# RaspberryPi-PICPgm.net
KiCad netlist of a schematic drawn in EAGLE
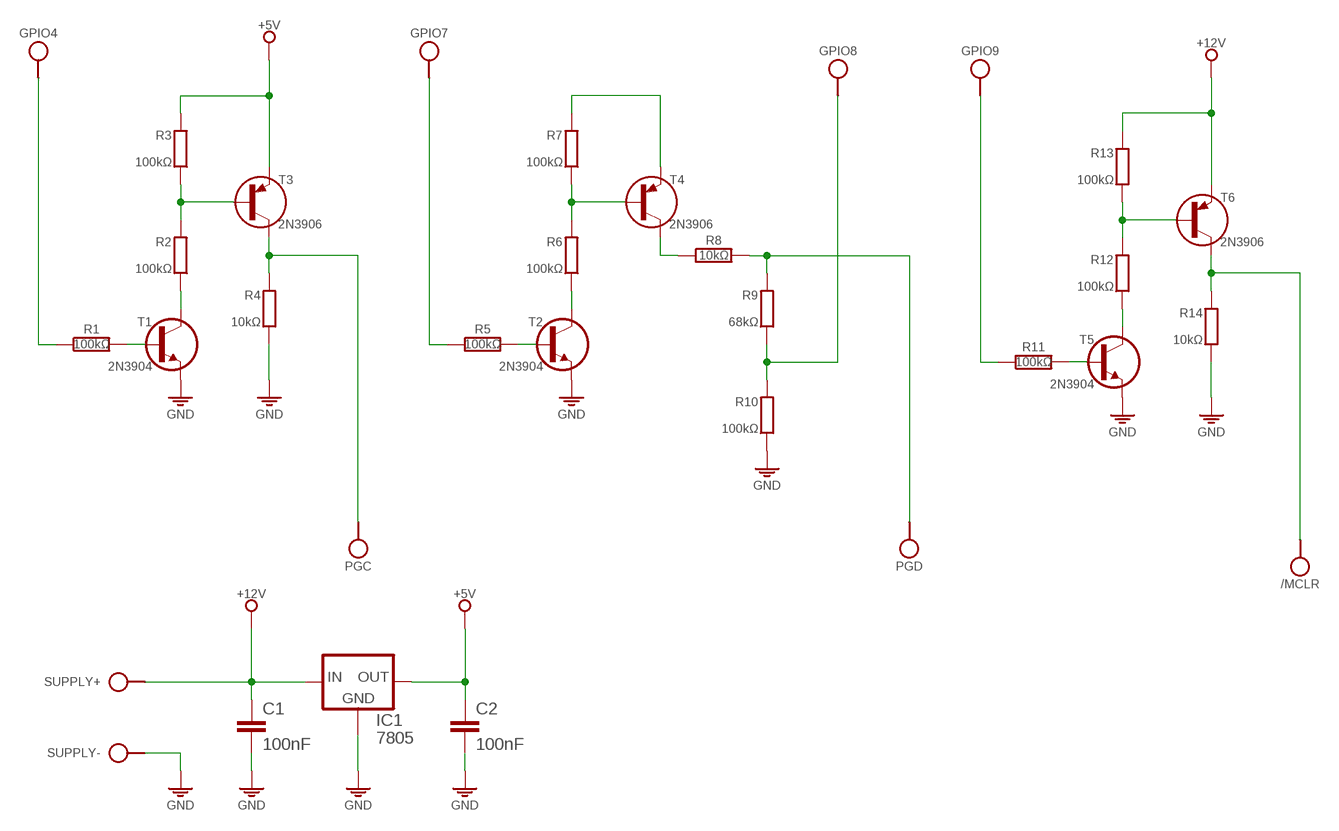
[diagram p0: schematic, sheet 1]

(export (version "E")
  (design (tool "Eeschema 10.0.6"))
  (components
    (comp (ref "/MCLR")
      (value "VPORT")
      (footprint "eagle-import:SPAD")
      (libsource (lib "eagle-import") (part "VPORT"))
    )
    (comp (ref "C1")
      (value "100nF")
      (footprint "eagle-import:C050-025X075")
      (libsource (lib "eagle-import") (part "C050-025X075"))
    )
    (comp (ref "C2")
      (value "100nF")
      (footprint "eagle-import:C050-025X075")
      (libsource (lib "eagle-import") (part "C050-025X075"))
    )
    (comp (ref "GPIO4")
      (value "VPORT")
      (footprint "eagle-import:SPAD")
      (libsource (lib "eagle-import") (part "VPORT"))
    )
    (comp (ref "GPIO7")
      (value "VPORT")
      (footprint "eagle-import:SPAD")
      (libsource (lib "eagle-import") (part "VPORT"))
    )
    (comp (ref "GPIO8")
      (value "VPORT")
      (footprint "eagle-import:SPAD")
      (libsource (lib "eagle-import") (part "VPORT"))
    )
    (comp (ref "GPIO9")
      (value "VPORT")
      (footprint "eagle-import:SPAD")
      (libsource (lib "eagle-import") (part "VPORT"))
    )
    (comp (ref "IC1")
      (value "7805")
      (footprint "eagle-import:TO220")
      (libsource (lib "eagle-import") (part "LM78"))
    )
    (comp (ref "PGC")
      (value "VPORT")
      (footprint "eagle-import:SPAD")
      (libsource (lib "eagle-import") (part "VPORT"))
    )
    (comp (ref "PGD")
      (value "VPORT")
      (footprint "eagle-import:SPAD")
      (libsource (lib "eagle-import") (part "VPORT"))
    )
    (comp (ref "R1")
      (value "100kΩ")
      (footprint "eagle-import:0204_10")
      (libsource (lib "eagle-import") (part "R-H0204/10"))
    )
    (comp (ref "R2")
      (value "100kΩ")
      (footprint "eagle-import:0204_10-V")
      (libsource (lib "eagle-import") (part "R0204/10-V"))
    )
    (comp (ref "R3")
      (value "100kΩ")
      (footprint "eagle-import:0204_10-V")
      (libsource (lib "eagle-import") (part "R0204/10-V"))
    )
    (comp (ref "R4")
      (value "10kΩ")
      (footprint "eagle-import:0204_10-V")
      (libsource (lib "eagle-import") (part "R0204/10-V"))
    )
    (comp (ref "R5")
      (value "100kΩ")
      (footprint "eagle-import:0204_10")
      (libsource (lib "eagle-import") (part "R-H0204/10"))
    )
    (comp (ref "R6")
      (value "100kΩ")
      (footprint "eagle-import:0204_10-V")
      (libsource (lib "eagle-import") (part "R0204/10-V"))
    )
    (comp (ref "R7")
      (value "100kΩ")
      (footprint "eagle-import:0204_10-V")
      (libsource (lib "eagle-import") (part "R0204/10-V"))
    )
    (comp (ref "R8")
      (value "10kΩ")
      (footprint "eagle-import:0204_10")
      (libsource (lib "eagle-import") (part "R-H0204/10"))
    )
    (comp (ref "R9")
      (value "68kΩ")
      (footprint "eagle-import:0204_10-V")
      (libsource (lib "eagle-import") (part "R0204/10-V"))
    )
    (comp (ref "R10")
      (value "100kΩ")
      (footprint "eagle-import:0204_10-V")
      (libsource (lib "eagle-import") (part "R0204/10-V"))
    )
    (comp (ref "R11")
      (value "100kΩ")
      (footprint "eagle-import:0204_10")
      (libsource (lib "eagle-import") (part "R-H0204/10"))
    )
    (comp (ref "R12")
      (value "100kΩ")
      (footprint "eagle-import:0204_10-V")
      (libsource (lib "eagle-import") (part "R0204/10-V"))
    )
    (comp (ref "R13")
      (value "100kΩ")
      (footprint "eagle-import:0204_10-V")
      (libsource (lib "eagle-import") (part "R0204/10-V"))
    )
    (comp (ref "R14")
      (value "10kΩ")
      (footprint "eagle-import:0204_10-V")
      (libsource (lib "eagle-import") (part "R0204/10-V"))
    )
    (comp (ref "SUPPLY")
      (value "SPAD+--+")
      (footprint "eagle-import:SPAD-+")
      (libsource (lib "eagle-import") (part "SPAD+--+"))
    )
    (comp (ref "T1")
      (value "2N3904")
      (footprint "eagle-import:TO92")
      (libsource (lib "eagle-import") (part "2N3904"))
    )
    (comp (ref "T2")
      (value "2N3904")
      (footprint "eagle-import:TO92")
      (libsource (lib "eagle-import") (part "2N3904"))
    )
    (comp (ref "T3")
      (value "2N3906")
      (footprint "eagle-import:TO92")
      (libsource (lib "eagle-import") (part "2N3906"))
    )
    (comp (ref "T4")
      (value "2N3906")
      (footprint "eagle-import:TO92")
      (libsource (lib "eagle-import") (part "2N3906"))
    )
    (comp (ref "T5")
      (value "2N3904")
      (footprint "eagle-import:TO92")
      (libsource (lib "eagle-import") (part "2N3904"))
    )
    (comp (ref "T6")
      (value "2N3906")
      (footprint "eagle-import:TO92")
      (libsource (lib "eagle-import") (part "2N3906"))
    )
  )
  (nets
    (net (code "1") (name "+5V") (class "Default")
      (node (ref "C2") (pin "1") (pinfunction "1_1") (pintype "passive"))
      (node (ref "IC1") (pin "3") (pinfunction "OUT_3") (pintype "output"))
      (node (ref "R3") (pin "1") (pinfunction "2_1") (pintype "passive"))
      (node (ref "R7") (pin "1") (pinfunction "2_1") (pintype "passive"))
      (node (ref "T3") (pin "1") (pinfunction "E_1") (pintype "passive"))
      (node (ref "T4") (pin "1") (pinfunction "E_1") (pintype "passive"))
    )
    (net (code "2") (name "+12V") (class "Default")
      (node (ref "C1") (pin "1") (pinfunction "1_1") (pintype "passive"))
      (node (ref "IC1") (pin "1") (pinfunction "IN_1") (pintype "input"))
      (node (ref "R13") (pin "1") (pinfunction "2_1") (pintype "passive"))
      (node (ref "SUPPLY") (pin "2") (pinfunction "P$1_2") (pintype "passive"))
      (node (ref "T6") (pin "1") (pinfunction "E_1") (pintype "passive"))
    )
    (net (code "3") (name "GND") (class "Default")
      (node (ref "C1") (pin "2") (pinfunction "2_2") (pintype "passive"))
      (node (ref "C2") (pin "2") (pinfunction "2_2") (pintype "passive"))
      (node (ref "IC1") (pin "2") (pinfunction "GND_2") (pintype "input"))
      (node (ref "R10") (pin "2") (pinfunction "1_2") (pintype "passive"))
      (node (ref "R14") (pin "2") (pinfunction "1_2") (pintype "passive"))
      (node (ref "R4") (pin "2") (pinfunction "1_2") (pintype "passive"))
      (node (ref "SUPPLY") (pin "1") (pinfunction "P$1_1") (pintype "passive"))
      (node (ref "T1") (pin "1") (pinfunction "E_1") (pintype "passive"))
      (node (ref "T2") (pin "1") (pinfunction "E_1") (pintype "passive"))
      (node (ref "T5") (pin "1") (pinfunction "E_1") (pintype "passive"))
    )
    (net (code "4") (name "Net-(/MCLR-P$1)") (class "Default")
      (node (ref "/MCLR") (pin "1") (pinfunction "P$1_1") (pintype "passive"))
      (node (ref "R14") (pin "1") (pinfunction "2_1") (pintype "passive"))
      (node (ref "T6") (pin "3") (pinfunction "C_3") (pintype "passive"))
    )
    (net (code "5") (name "Net-(GPIO4-P$1)") (class "Default")
      (node (ref "GPIO4") (pin "1") (pinfunction "P$1_1") (pintype "passive"))
      (node (ref "R1") (pin "1") (pinfunction "1_1") (pintype "passive"))
    )
    (net (code "6") (name "Net-(GPIO7-P$1)") (class "Default")
      (node (ref "GPIO7") (pin "1") (pinfunction "P$1_1") (pintype "passive"))
      (node (ref "R5") (pin "1") (pinfunction "1_1") (pintype "passive"))
    )
    (net (code "7") (name "Net-(GPIO8-P$1)") (class "Default")
      (node (ref "GPIO8") (pin "1") (pinfunction "P$1_1") (pintype "passive"))
      (node (ref "R10") (pin "1") (pinfunction "2_1") (pintype "passive"))
      (node (ref "R9") (pin "2") (pinfunction "1_2") (pintype "passive"))
    )
    (net (code "8") (name "Net-(GPIO9-P$1)") (class "Default")
      (node (ref "GPIO9") (pin "1") (pinfunction "P$1_1") (pintype "passive"))
      (node (ref "R11") (pin "1") (pinfunction "1_1") (pintype "passive"))
    )
    (net (code "9") (name "Net-(PGC-P$1)") (class "Default")
      (node (ref "PGC") (pin "1") (pinfunction "P$1_1") (pintype "passive"))
      (node (ref "R4") (pin "1") (pinfunction "2_1") (pintype "passive"))
      (node (ref "T3") (pin "3") (pinfunction "C_3") (pintype "passive"))
    )
    (net (code "10") (name "Net-(PGD-P$1)") (class "Default")
      (node (ref "PGD") (pin "1") (pinfunction "P$1_1") (pintype "passive"))
      (node (ref "R8") (pin "2") (pinfunction "2_2") (pintype "passive"))
      (node (ref "R9") (pin "1") (pinfunction "2_1") (pintype "passive"))
    )
    (net (code "11") (name "Net-(R2-1)") (class "Default")
      (node (ref "R2") (pin "2") (pinfunction "1_2") (pintype "passive"))
      (node (ref "T1") (pin "3") (pinfunction "C_3") (pintype "passive"))
    )
    (net (code "12") (name "Net-(R2-2)") (class "Default")
      (node (ref "R2") (pin "1") (pinfunction "2_1") (pintype "passive"))
      (node (ref "R3") (pin "2") (pinfunction "1_2") (pintype "passive"))
      (node (ref "T3") (pin "2") (pinfunction "B_2") (pintype "passive"))
    )
    (net (code "13") (name "Net-(R6-1)") (class "Default")
      (node (ref "R6") (pin "2") (pinfunction "1_2") (pintype "passive"))
      (node (ref "T2") (pin "3") (pinfunction "C_3") (pintype "passive"))
    )
    (net (code "14") (name "Net-(R6-2)") (class "Default")
      (node (ref "R6") (pin "1") (pinfunction "2_1") (pintype "passive"))
      (node (ref "R7") (pin "2") (pinfunction "1_2") (pintype "passive"))
      (node (ref "T4") (pin "2") (pinfunction "B_2") (pintype "passive"))
    )
    (net (code "15") (name "Net-(R12-1)") (class "Default")
      (node (ref "R12") (pin "2") (pinfunction "1_2") (pintype "passive"))
      (node (ref "T5") (pin "3") (pinfunction "C_3") (pintype "passive"))
    )
    (net (code "16") (name "Net-(R12-2)") (class "Default")
      (node (ref "R12") (pin "1") (pinfunction "2_1") (pintype "passive"))
      (node (ref "R13") (pin "2") (pinfunction "1_2") (pintype "passive"))
      (node (ref "T6") (pin "2") (pinfunction "B_2") (pintype "passive"))
    )
    (net (code "17") (name "Net-(T1-B)") (class "Default")
      (node (ref "R1") (pin "2") (pinfunction "2_2") (pintype "passive"))
      (node (ref "T1") (pin "2") (pinfunction "B_2") (pintype "passive"))
    )
    (net (code "18") (name "Net-(T2-B)") (class "Default")
      (node (ref "R5") (pin "2") (pinfunction "2_2") (pintype "passive"))
      (node (ref "T2") (pin "2") (pinfunction "B_2") (pintype "passive"))
    )
    (net (code "19") (name "Net-(T4-C)") (class "Default")
      (node (ref "R8") (pin "1") (pinfunction "1_1") (pintype "passive"))
      (node (ref "T4") (pin "3") (pinfunction "C_3") (pintype "passive"))
    )
    (net (code "20") (name "Net-(T5-B)") (class "Default")
      (node (ref "R11") (pin "2") (pinfunction "2_2") (pintype "passive"))
      (node (ref "T5") (pin "2") (pinfunction "B_2") (pintype "passive"))
    )
  )
)
